# schematic.net
KiCad netlist of a schematic drawn in EAGLE
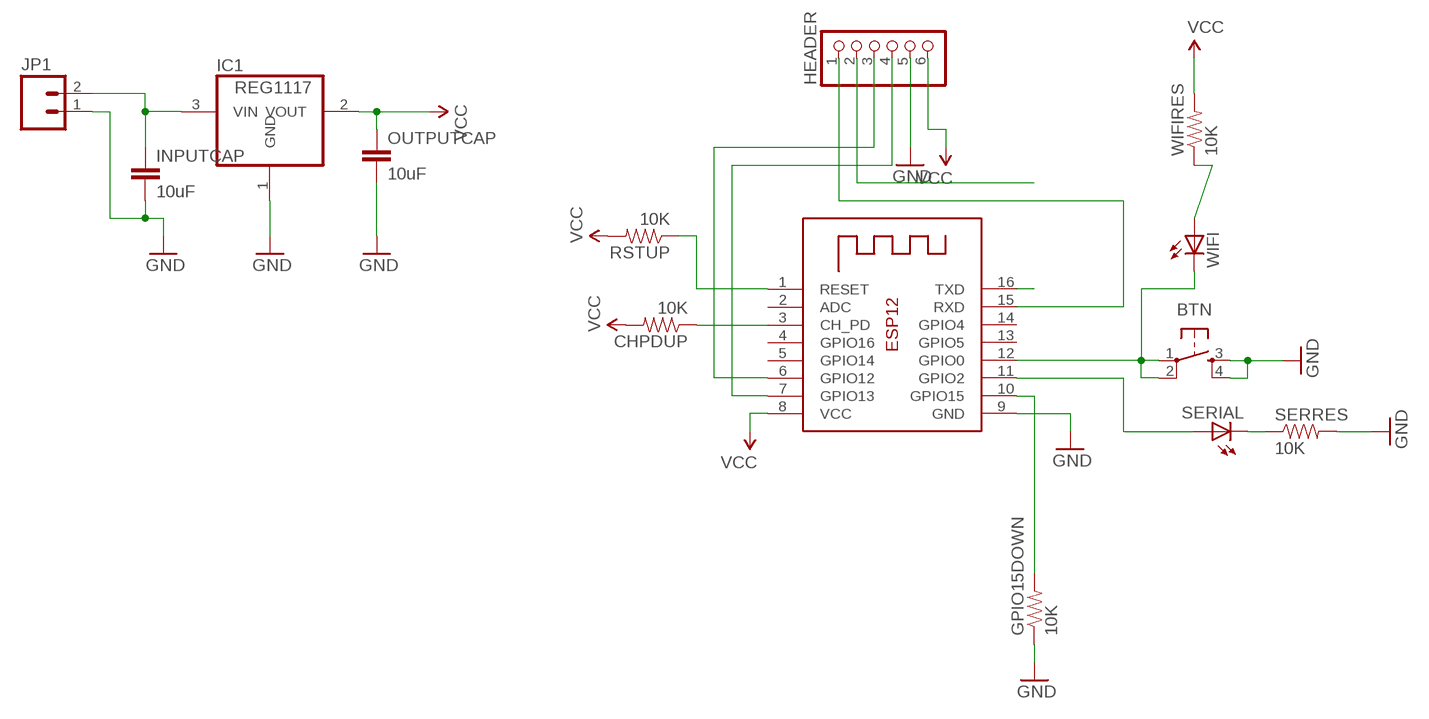
[diagram p0: schematic, sheet 1]

(export (version "E")
  (design (tool "Eeschema 10.0.6"))
  (components
    (comp (ref "BTN")
      (value "TAC_SWITCHPTH")
      (footprint "eagle-import:TACTILE-PTH")
      (libsource (lib "eagle-import") (part "TAC_SWITCHPTH"))
    )
    (comp (ref "CHPDUP")
      (value "10K")
      (footprint "eagle-import:0805")
      (libsource (lib "eagle-import") (part "RESISTOR0805-RES"))
    )
    (comp (ref "GPIO15DOWN")
      (value "10K")
      (footprint "eagle-import:0805")
      (libsource (lib "eagle-import") (part "RESISTOR0805-RES"))
    )
    (comp (ref "HEADER")
      (value "PINHD-1X6")
      (footprint "eagle-import:1X06")
      (libsource (lib "eagle-import") (part "PINHD-1X6"))
    )
    (comp (ref "IC1")
      (value "REG1117")
      (footprint "eagle-import:SOT223")
      (libsource (lib "eagle-import") (part "REG1117"))
    )
    (comp (ref "INPUTCAP")
      (value "10uF")
      (footprint "eagle-import:0805")
      (libsource (lib "eagle-import") (part "CAP0805"))
    )
    (comp (ref "JP1")
      (value "M02LOCK")
      (footprint "eagle-import:1X02_LOCK")
      (libsource (lib "eagle-import") (part "M02LOCK"))
    )
    (comp (ref "OUTPUTCAP")
      (value "10uF")
      (footprint "eagle-import:0805")
      (libsource (lib "eagle-import") (part "CAP0805"))
    )
    (comp (ref "RSTUP")
      (value "10K")
      (footprint "eagle-import:0805")
      (libsource (lib "eagle-import") (part "RESISTOR0805-RES"))
    )
    (comp (ref "SERIAL")
      (value "LEDCHIPLED_0805")
      (footprint "eagle-import:CHIPLED_0805")
      (libsource (lib "eagle-import") (part "LEDCHIPLED_0805"))
    )
    (comp (ref "SERRES")
      (value "10K")
      (footprint "eagle-import:0805")
      (libsource (lib "eagle-import") (part "RESISTOR0805-RES"))
    )
    (comp (ref "WIFI")
      (value "LEDCHIPLED_0805")
      (footprint "eagle-import:CHIPLED_0805")
      (libsource (lib "eagle-import") (part "LEDCHIPLED_0805"))
    )
    (comp (ref "WIFIRES")
      (value "10K")
      (footprint "eagle-import:0805")
      (libsource (lib "eagle-import") (part "RESISTOR0805-RES"))
    )
    (comp (ref "X1")
      (value "ESP-12")
      (footprint "eagle-import:ESP-12")
      (libsource (lib "eagle-import") (part "ESP-12"))
    )
  )
  (nets
    (net (code "1") (name "GND") (class "Default")
      (node (ref "BTN") (pin "3") (pinfunction "3_3") (pintype "passive"))
      (node (ref "BTN") (pin "4") (pinfunction "4_4") (pintype "passive"))
      (node (ref "GPIO15DOWN") (pin "1") (pinfunction "1_1") (pintype "passive"))
      (node (ref "HEADER") (pin "5") (pinfunction "5_5") (pintype "passive"))
      (node (ref "IC1") (pin "1") (pinfunction "GND_1") (pintype "power_in"))
      (node (ref "INPUTCAP") (pin "2") (pinfunction "2_2") (pintype "passive"))
      (node (ref "JP1") (pin "1") (pinfunction "1_1") (pintype "passive"))
      (node (ref "OUTPUTCAP") (pin "2") (pinfunction "2_2") (pintype "passive"))
      (node (ref "SERRES") (pin "2") (pinfunction "2_2") (pintype "passive"))
      (node (ref "X1") (pin "9") (pinfunction "GND_9") (pintype "power_in"))
    )
    (net (code "2") (name "Net-(IC1-VIN)") (class "Default")
      (node (ref "IC1") (pin "3") (pinfunction "VIN_3") (pintype "input"))
      (node (ref "INPUTCAP") (pin "1") (pinfunction "1_1") (pintype "passive"))
      (node (ref "JP1") (pin "2") (pinfunction "2_2") (pintype "passive"))
    )
    (net (code "3") (name "Net-(SERIAL-PadC)") (class "Default")
      (node (ref "SERIAL") (pin "C") (pinfunction "C_C") (pintype "passive"))
      (node (ref "SERRES") (pin "1") (pinfunction "1_1") (pintype "passive"))
    )
    (net (code "4") (name "Net-(WIFI-PadA)") (class "Default")
      (node (ref "WIFI") (pin "A") (pinfunction "A_A") (pintype "passive"))
      (node (ref "WIFIRES") (pin "1") (pinfunction "1_1") (pintype "passive"))
    )
    (net (code "5") (name "Net-(X1-CH_PD)") (class "Default")
      (node (ref "CHPDUP") (pin "1") (pinfunction "1_1") (pintype "passive"))
      (node (ref "X1") (pin "3") (pinfunction "CH_PD_3") (pintype "input"))
    )
    (net (code "6") (name "Net-(X1-GPIO0)") (class "Default")
      (node (ref "BTN") (pin "1") (pinfunction "1_1") (pintype "passive"))
      (node (ref "BTN") (pin "2") (pinfunction "2_2") (pintype "passive"))
      (node (ref "WIFI") (pin "C") (pinfunction "C_C") (pintype "passive"))
      (node (ref "X1") (pin "12") (pinfunction "GPIO0_12") (pintype "bidirectional"))
    )
    (net (code "7") (name "Net-(X1-GPIO2)") (class "Default")
      (node (ref "SERIAL") (pin "A") (pinfunction "A_A") (pintype "passive"))
      (node (ref "X1") (pin "11") (pinfunction "GPIO2_11") (pintype "bidirectional"))
    )
    (net (code "8") (name "Net-(X1-GPIO12)") (class "Default")
      (node (ref "HEADER") (pin "3") (pinfunction "3_3") (pintype "passive"))
      (node (ref "X1") (pin "6") (pinfunction "GPIO12_6") (pintype "bidirectional"))
    )
    (net (code "9") (name "Net-(X1-GPIO13)") (class "Default")
      (node (ref "HEADER") (pin "4") (pinfunction "4_4") (pintype "passive"))
      (node (ref "X1") (pin "7") (pinfunction "GPIO13_7") (pintype "bidirectional"))
    )
    (net (code "10") (name "Net-(X1-GPIO15)") (class "Default")
      (node (ref "GPIO15DOWN") (pin "2") (pinfunction "2_2") (pintype "passive"))
      (node (ref "X1") (pin "10") (pinfunction "GPIO15_10") (pintype "bidirectional"))
    )
    (net (code "11") (name "Net-(X1-RESET)") (class "Default")
      (node (ref "RSTUP") (pin "1") (pinfunction "1_1") (pintype "passive"))
      (node (ref "X1") (pin "1") (pinfunction "RESET_1") (pintype "input"))
    )
    (net (code "12") (name "Net-(X1-RXD)") (class "Default")
      (node (ref "HEADER") (pin "1") (pinfunction "1_1") (pintype "passive"))
      (node (ref "X1") (pin "15") (pinfunction "RXD_15") (pintype "input"))
    )
    (net (code "13") (name "VCC") (class "Default")
      (node (ref "CHPDUP") (pin "2") (pinfunction "2_2") (pintype "passive"))
      (node (ref "HEADER") (pin "6") (pinfunction "6_6") (pintype "passive"))
      (node (ref "IC1") (pin "2") (pinfunction "VOUT_2") (pintype "output"))
      (node (ref "OUTPUTCAP") (pin "1") (pinfunction "1_1") (pintype "passive"))
      (node (ref "RSTUP") (pin "2") (pinfunction "2_2") (pintype "passive"))
      (node (ref "WIFIRES") (pin "2") (pinfunction "2_2") (pintype "passive"))
      (node (ref "X1") (pin "8") (pinfunction "VCC_8") (pintype "power_in"))
    )
    (net (code "14") (name "unconnected-(HEADER-Pad2)") (class "Default")
      (node (ref "HEADER") (pin "2") (pinfunction "2_2") (pintype "passive"))
    )
    (net (code "15") (name "unconnected-(X1-ADC-Pad2)") (class "Default")
      (node (ref "X1") (pin "2") (pinfunction "ADC_2") (pintype "passive"))
    )
    (net (code "16") (name "unconnected-(X1-GPIO4-Pad14)") (class "Default")
      (node (ref "X1") (pin "14") (pinfunction "GPIO4_14") (pintype "bidirectional"))
    )
    (net (code "17") (name "unconnected-(X1-GPIO5-Pad13)") (class "Default")
      (node (ref "X1") (pin "13") (pinfunction "GPIO5_13") (pintype "bidirectional"))
    )
    (net (code "18") (name "unconnected-(X1-GPIO14-Pad5)") (class "Default")
      (node (ref "X1") (pin "5") (pinfunction "GPIO14_5") (pintype "bidirectional"))
    )
    (net (code "19") (name "unconnected-(X1-GPIO16-Pad4)") (class "Default")
      (node (ref "X1") (pin "4") (pinfunction "GPIO16_4") (pintype "bidirectional"))
    )
    (net (code "20") (name "unconnected-(X1-TXD-Pad16)") (class "Default")
      (node (ref "X1") (pin "16") (pinfunction "TXD_16") (pintype "output"))
    )
  )
)
